# mapleCUx_large_088-Stripped.net
KiCad netlist of a schematic drawn in EAGLE
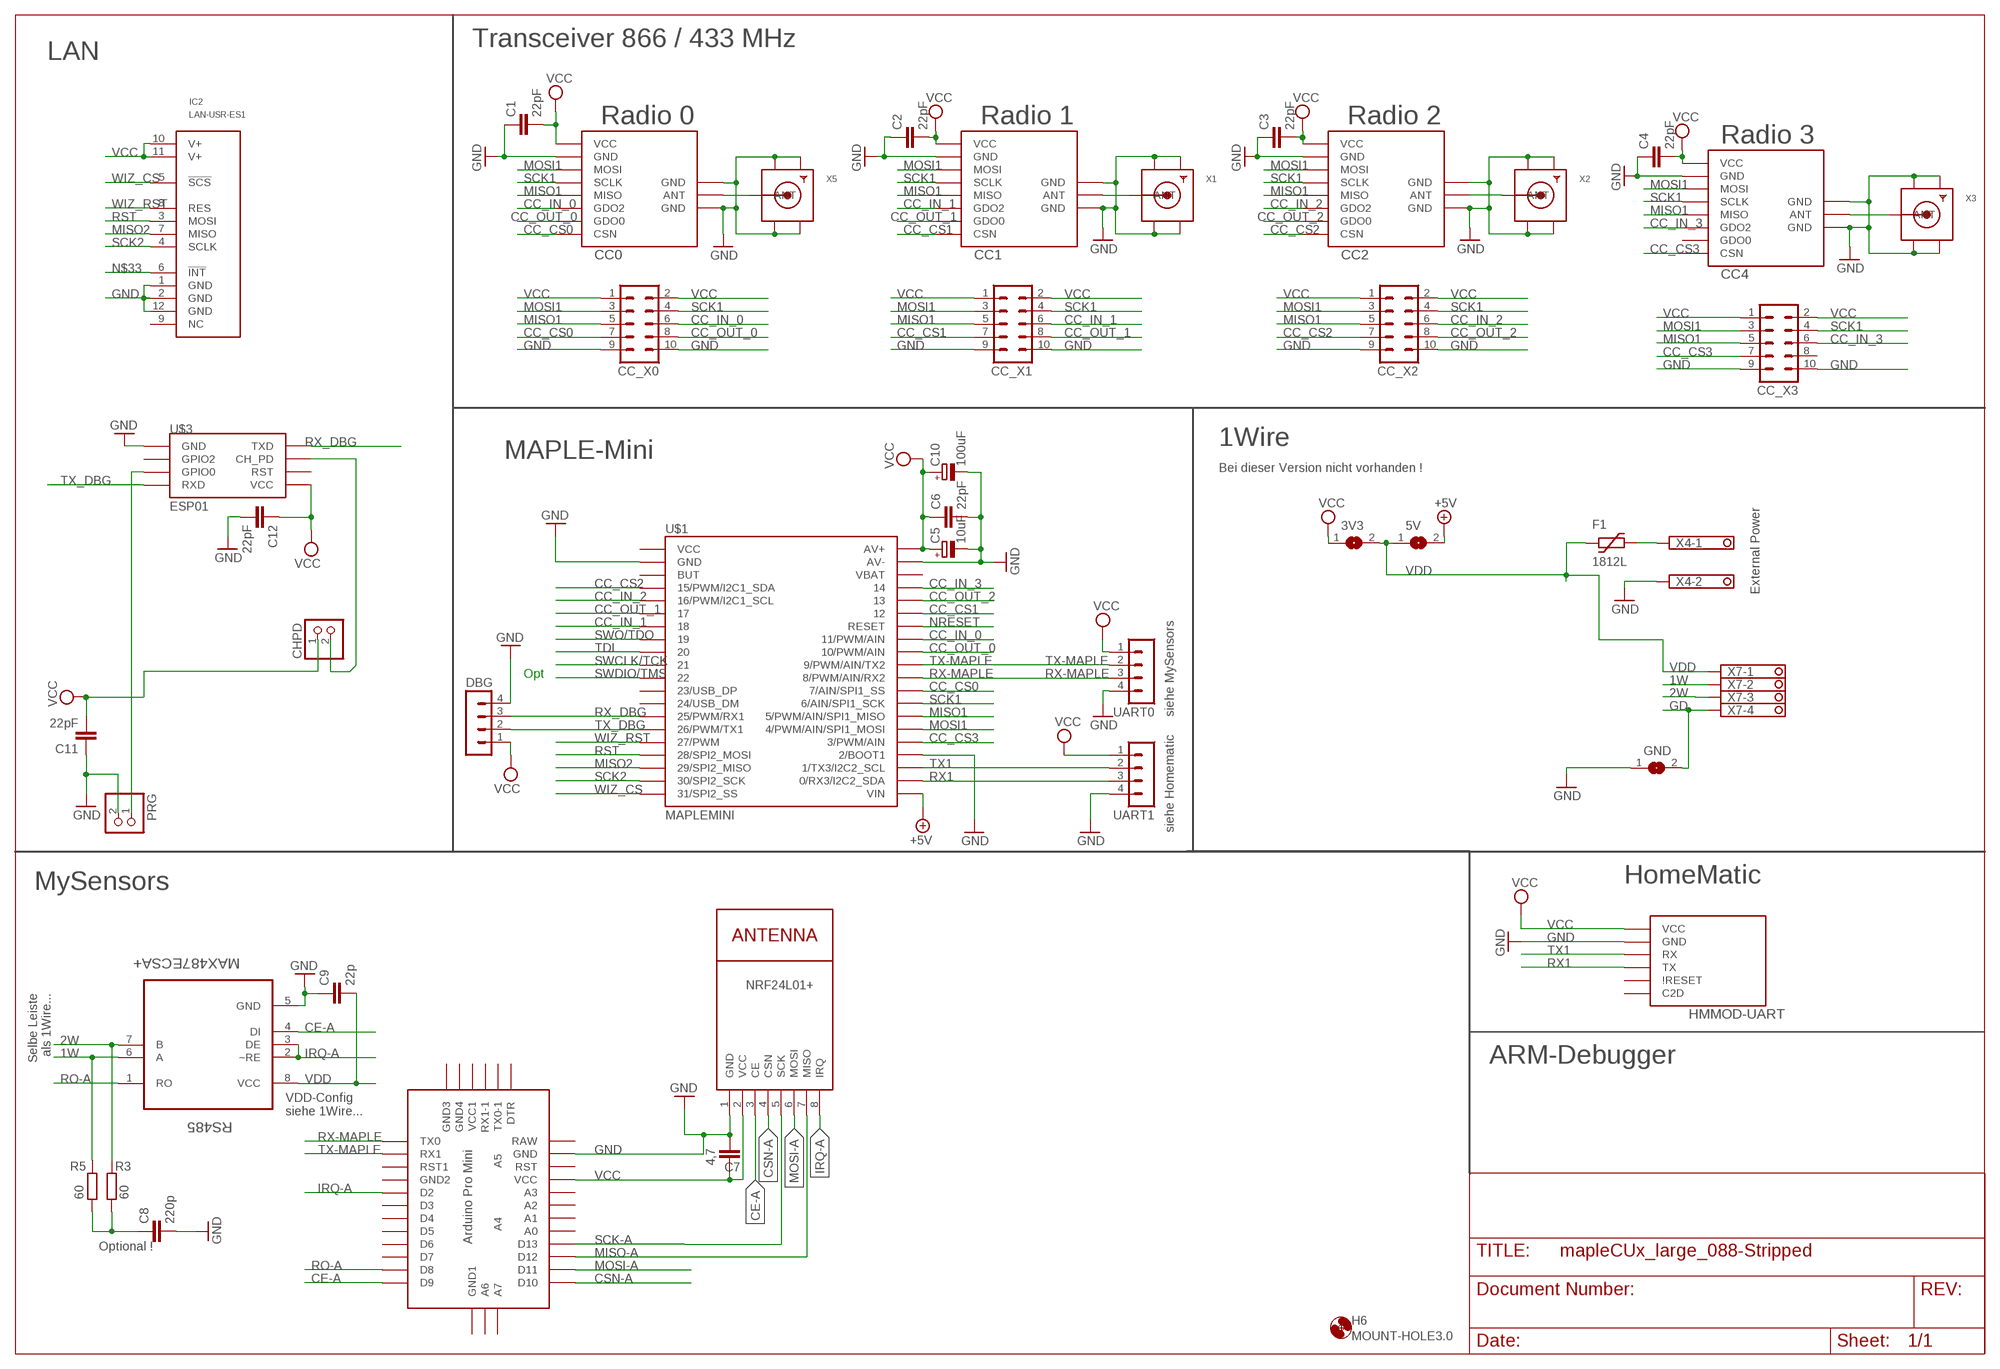
[diagram p0: schematic, sheet 1]

(export (version "E")
  (design (tool "Eeschema 10.0.6"))
  (components
    (comp (ref "3V3") (value "SJ") (footprint "eagle-import:SJ") (libsource (lib "eagle-import") (part "SJ")))
    (comp (ref "5V") (value "SJ") (footprint "eagle-import:SJ") (libsource (lib "eagle-import") (part "SJ")))
    (comp (ref "C1")
      (value "22pF")
      (footprint "eagle-import:C0805")
      (libsource (lib "eagle-import") (part "C-EUC0805"))
    )
    (comp (ref "C2")
      (value "22pF")
      (footprint "eagle-import:C0805")
      (libsource (lib "eagle-import") (part "C-EUC0805"))
    )
    (comp (ref "C3")
      (value "22pF")
      (footprint "eagle-import:C0805")
      (libsource (lib "eagle-import") (part "C-EUC0805"))
    )
    (comp (ref "C4")
      (value "22pF")
      (footprint "eagle-import:C0805")
      (libsource (lib "eagle-import") (part "C-EUC0805"))
    )
    (comp (ref "C5")
      (value "10uF")
      (footprint "eagle-import:R_2012-12W")
      (libsource (lib "eagle-import") (part "CPOL-EUR/2012-12W"))
    )
    (comp (ref "C6")
      (value "22pF")
      (footprint "eagle-import:C0805")
      (libsource (lib "eagle-import") (part "C-EUC0805"))
    )
    (comp (ref "C7")
      (value "4,7")
      (footprint "eagle-import:C1210")
      (libsource (lib "eagle-import") (part "C-EUC1210"))
    )
    (comp (ref "C8")
      (value "220p")
      (footprint "eagle-import:C0805")
      (libsource (lib "eagle-import") (part "C-EUC0805"))
    )
    (comp (ref "C9")
      (value "22p")
      (footprint "eagle-import:C0805")
      (libsource (lib "eagle-import") (part "C-EUC0805"))
    )
    (comp (ref "C10")
      (value "100uF")
      (footprint "eagle-import:E5-8,5")
      (libsource (lib "eagle-import") (part "CPOL-EUE5-8.5"))
    )
    (comp (ref "C11")
      (value "22pF")
      (footprint "eagle-import:C0805")
      (libsource (lib "eagle-import") (part "C-EUC0805"))
    )
    (comp (ref "C12")
      (value "22pF")
      (footprint "eagle-import:C0805")
      (libsource (lib "eagle-import") (part "C-EUC0805"))
    )
    (comp (ref "CC0")
      (value "CC1101")
      (footprint "eagle-import:CC1101_MODULE1_SMD")
      (libsource (lib "eagle-import") (part "CC1101_MODULE1SMD"))
    )
    (comp (ref "CC1")
      (value "CC1101_MODULE1SMD")
      (footprint "eagle-import:CC1101_MODULE1_SMD")
      (libsource (lib "eagle-import") (part "CC1101_MODULE1SMD"))
    )
    (comp (ref "CC2")
      (value "CC1101_MODULE1SMD")
      (footprint "eagle-import:CC1101_MODULE1_SMD")
      (libsource (lib "eagle-import") (part "CC1101_MODULE1SMD"))
    )
    (comp (ref "CC4")
      (value "CC1101_MODULE1SMD")
      (footprint "eagle-import:CC1101_MODULE1_SMD")
      (libsource (lib "eagle-import") (part "CC1101_MODULE1SMD"))
    )
    (comp (ref "CC_X0")
      (value "MA05-2")
      (footprint "eagle-import:MA05-2")
      (libsource (lib "eagle-import") (part "MA05-2"))
    )
    (comp (ref "CC_X1")
      (value "MA05-2")
      (footprint "eagle-import:MA05-2")
      (libsource (lib "eagle-import") (part "MA05-2"))
    )
    (comp (ref "CC_X2")
      (value "MA05-2")
      (footprint "eagle-import:MA05-2")
      (libsource (lib "eagle-import") (part "MA05-2"))
    )
    (comp (ref "CC_X3")
      (value "MA05-2")
      (footprint "eagle-import:MA05-2")
      (libsource (lib "eagle-import") (part "MA05-2"))
    )
    (comp (ref "CHPD")
      (value "PINHD-1X2")
      (footprint "eagle-import:1X02")
      (libsource (lib "eagle-import") (part "PINHD-1X2"))
    )
    (comp (ref "DBG")
      (value "MA04-1")
      (footprint "eagle-import:MA04-1")
      (libsource (lib "eagle-import") (part "MA04-1"))
    )
    (comp (ref "F1")
      (value "1812L")
      (footprint "eagle-import:1812L")
      (libsource (lib "eagle-import") (part "1812L"))
    )
    (comp (ref "GND") (value "SJ") (footprint "eagle-import:SJ") (libsource (lib "eagle-import") (part "SJ")))
    (comp (ref "H6")
      (value "MOUNT-HOLE3.0")
      (footprint "eagle-import:3,0")
      (libsource (lib "eagle-import") (part "MOUNT-HOLE3.0"))
    )
    (comp (ref "HMMOD-UART")
      (value "HM-MOD-UARTDIL")
      (footprint "eagle-import:HM-MOD-UART-DIL")
      (libsource (lib "eagle-import") (part "HM-MOD-UARTDIL"))
    )
    (comp (ref "IC2")
      (value "LAN-USR-ES1")
      (footprint "eagle-import:USR-ES1")
      (libsource (lib "eagle-import") (part "LAN-USR-ES1"))
    )
    (comp (ref "NRF24L01+")
      (value "NRF24L01+")
      (footprint "eagle-import:WIRELESS-NRF24L01")
      (libsource (lib "eagle-import") (part "WIRELESS-NRF24L01"))
    )
    (comp (ref "PRG")
      (value "PINHD-1X2")
      (footprint "eagle-import:1X02")
      (libsource (lib "eagle-import") (part "PINHD-1X2"))
    )
    (comp (ref "R3")
      (value "60")
      (footprint "eagle-import:R0805")
      (libsource (lib "eagle-import") (part "R-EU_R0805"))
    )
    (comp (ref "R5")
      (value "60")
      (footprint "eagle-import:R0805")
      (libsource (lib "eagle-import") (part "R-EU_R0805"))
    )
    (comp (ref "RS485")
      (value "MAX487ECSA+")
      (footprint "eagle-import:SOIC127P600X175-8N")
      (libsource (lib "eagle-import") (part "MAX487ECSA+"))
    )
    (comp (ref "U$1")
      (value "MAPLEMINI")
      (footprint "eagle-import:20-DIP")
      (libsource (lib "eagle-import") (part "MAPLEMINI"))
    )
    (comp (ref "U$2")
      (value "ABK-PRO-MINI")
      (footprint "eagle-import:ABK-PRO-MINI")
      (libsource (lib "eagle-import") (part "ABK-PRO-MINI"))
    )
    (comp (ref "U$3")
      (value "ESP01")
      (footprint "eagle-import:ESP01")
      (libsource (lib "eagle-import") (part "ESP01"))
    )
    (comp (ref "UART0")
      (value "MA04-1")
      (footprint "eagle-import:MA04-1")
      (libsource (lib "eagle-import") (part "MA04-1"))
    )
    (comp (ref "UART1")
      (value "MA04-1")
      (footprint "eagle-import:MA04-1")
      (libsource (lib "eagle-import") (part "MA04-1"))
    )
    (comp (ref "X1")
      (value "SMACONNECTOR_EDGE_UFL")
      (footprint "eagle-import:SMA_EDGELAUNCH_UFL")
      (libsource (lib "eagle-import") (part "SMACONNECTOR_EDGE_UFL"))
    )
    (comp (ref "X2")
      (value "SMACONNECTOR_EDGE_UFL")
      (footprint "eagle-import:SMA_EDGELAUNCH_UFL")
      (libsource (lib "eagle-import") (part "SMACONNECTOR_EDGE_UFL"))
    )
    (comp (ref "X3")
      (value "SMACONNECTOR_EDGE_UFL")
      (footprint "eagle-import:SMA_EDGELAUNCH_UFL")
      (libsource (lib "eagle-import") (part "SMACONNECTOR_EDGE_UFL"))
    )
    (comp (ref "X4")
      (value "1751248")
      (footprint "eagle-import:1751248")
      (libsource (lib "eagle-import") (part "1751248"))
    )
    (comp (ref "X5")
      (value "SMACONNECTOR_EDGE_UFL")
      (footprint "eagle-import:SMA_EDGELAUNCH_UFL")
      (libsource (lib "eagle-import") (part "SMACONNECTOR_EDGE_UFL"))
    )
    (comp (ref "X7")
      (value "1751264")
      (footprint "eagle-import:1751264")
      (libsource (lib "eagle-import") (part "1751264"))
    )
  )
  (nets
    (net (code "1") (name "+5V") (class "Default")
      (node (ref "5V") (pin "2") (pinfunction "2_2") (pintype "passive"))
      (node (ref "U$1") (pin "21") (pinfunction "VIN_21") (pintype "bidirectional"))
    )
    (net (code "2") (name "/1W") (class "Default")
      (node (ref "R5") (pin "2") (pinfunction "2_2") (pintype "passive"))
      (node (ref "RS485") (pin "6") (pinfunction "A_6") (pintype "bidirectional"))
      (node (ref "X7") (pin "2") (pinfunction "K_2") (pintype "passive"))
    )
    (net (code "3") (name "/2W") (class "Default")
      (node (ref "R3") (pin "2") (pinfunction "2_2") (pintype "passive"))
      (node (ref "RS485") (pin "7") (pinfunction "B_7") (pintype "bidirectional"))
      (node (ref "X7") (pin "3") (pinfunction "K_3") (pintype "passive"))
    )
    (net (code "4") (name "/CC_CS0") (class "Default")
      (node (ref "CC0") (pin "CSN") (pinfunction "CSN_CSN") (pintype "bidirectional"))
      (node (ref "CC_X0") (pin "7") (pinfunction "7_7") (pintype "passive"))
      (node (ref "U$1") (pin "29") (pinfunction "7/AIN/SPI1_SS_29") (pintype "bidirectional"))
    )
    (net (code "5") (name "/CC_CS1") (class "Default")
      (node (ref "CC1") (pin "CSN") (pinfunction "CSN_CSN") (pintype "bidirectional"))
      (node (ref "CC_X1") (pin "7") (pinfunction "7_7") (pintype "passive"))
      (node (ref "U$1") (pin "35") (pinfunction "12_35") (pintype "bidirectional"))
    )
    (net (code "6") (name "/CC_CS2") (class "Default")
      (node (ref "CC2") (pin "CSN") (pinfunction "CSN_CSN") (pintype "bidirectional"))
      (node (ref "CC_X2") (pin "7") (pinfunction "7_7") (pintype "passive"))
      (node (ref "U$1") (pin "4") (pinfunction "15/PWM/I2C1_SDA_4") (pintype "bidirectional"))
    )
    (net (code "7") (name "/CC_CS3") (class "Default")
      (node (ref "CC4") (pin "CSN") (pinfunction "CSN_CSN") (pintype "bidirectional"))
      (node (ref "CC_X3") (pin "7") (pinfunction "7_7") (pintype "passive"))
      (node (ref "U$1") (pin "25") (pinfunction "3/PWM/AIN_25") (pintype "bidirectional"))
    )
    (net (code "8") (name "/CC_IN_0") (class "Default")
      (node (ref "CC0") (pin "GDO2") (pinfunction "GDO2_GDO2") (pintype "bidirectional"))
      (node (ref "CC_X0") (pin "6") (pinfunction "6_6") (pintype "passive"))
      (node (ref "U$1") (pin "33") (pinfunction "11/PWM/AIN_33") (pintype "bidirectional"))
    )
    (net (code "9") (name "/CC_IN_1") (class "Default")
      (node (ref "CC1") (pin "GDO2") (pinfunction "GDO2_GDO2") (pintype "bidirectional"))
      (node (ref "CC_X1") (pin "6") (pinfunction "6_6") (pintype "passive"))
      (node (ref "U$1") (pin "7") (pinfunction "18_7") (pintype "bidirectional"))
    )
    (net (code "10") (name "/CC_IN_2") (class "Default")
      (node (ref "CC2") (pin "GDO2") (pinfunction "GDO2_GDO2") (pintype "bidirectional"))
      (node (ref "CC_X2") (pin "6") (pinfunction "6_6") (pintype "passive"))
      (node (ref "U$1") (pin "5") (pinfunction "16/PWM/I2C1_SCL_5") (pintype "bidirectional"))
    )
    (net (code "11") (name "/CC_IN_3") (class "Default")
      (node (ref "CC4") (pin "GDO2") (pinfunction "GDO2_GDO2") (pintype "bidirectional"))
      (node (ref "CC_X3") (pin "6") (pinfunction "6_6") (pintype "passive"))
      (node (ref "U$1") (pin "37") (pinfunction "14_37") (pintype "bidirectional"))
    )
    (net (code "12") (name "/CC_OUT_0") (class "Default")
      (node (ref "CC0") (pin "GDO0") (pinfunction "GDO0_GDO0") (pintype "bidirectional"))
      (node (ref "CC_X0") (pin "8") (pinfunction "8_8") (pintype "passive"))
      (node (ref "U$1") (pin "32") (pinfunction "10/PWM/AIN_32") (pintype "bidirectional"))
    )
    (net (code "13") (name "/CC_OUT_1") (class "Default")
      (node (ref "CC1") (pin "GDO0") (pinfunction "GDO0_GDO0") (pintype "bidirectional"))
      (node (ref "CC_X1") (pin "8") (pinfunction "8_8") (pintype "passive"))
      (node (ref "U$1") (pin "6") (pinfunction "17_6") (pintype "bidirectional"))
    )
    (net (code "14") (name "/CC_OUT_2") (class "Default")
      (node (ref "CC2") (pin "GDO0") (pinfunction "GDO0_GDO0") (pintype "bidirectional"))
      (node (ref "CC_X2") (pin "8") (pinfunction "8_8") (pintype "passive"))
      (node (ref "U$1") (pin "36") (pinfunction "13_36") (pintype "bidirectional"))
    )
    (net (code "15") (name "/GD") (class "Default")
      (node (ref "GND") (pin "2") (pinfunction "2_2") (pintype "passive"))
      (node (ref "X7") (pin "4") (pinfunction "K_4") (pintype "passive"))
    )
    (net (code "16") (name "/MISO-A") (class "Default")
      (node (ref "NRF24L01+") (pin "7") (pinfunction "MISO_7") (pintype "bidirectional"))
      (node (ref "U$2") (pin "D12") (pinfunction "D12_D12") (pintype "bidirectional"))
    )
    (net (code "17") (name "/MISO1") (class "Default")
      (node (ref "CC0") (pin "MISO") (pinfunction "MISO_MISO") (pintype "bidirectional"))
      (node (ref "CC1") (pin "MISO") (pinfunction "MISO_MISO") (pintype "bidirectional"))
      (node (ref "CC2") (pin "MISO") (pinfunction "MISO_MISO") (pintype "bidirectional"))
      (node (ref "CC4") (pin "MISO") (pinfunction "MISO_MISO") (pintype "bidirectional"))
      (node (ref "CC_X0") (pin "5") (pinfunction "5_5") (pintype "passive"))
      (node (ref "CC_X1") (pin "5") (pinfunction "5_5") (pintype "passive"))
      (node (ref "CC_X2") (pin "5") (pinfunction "5_5") (pintype "passive"))
      (node (ref "CC_X3") (pin "5") (pinfunction "5_5") (pintype "passive"))
      (node (ref "U$1") (pin "27") (pinfunction "5/PWM/AIN/SPI1_MISO_27") (pintype "bidirectional"))
    )
    (net (code "18") (name "/MISO2") (class "Default")
      (node (ref "IC2") (pin "7") (pinfunction "MISO_7") (pintype "bidirectional"))
      (node (ref "U$1") (pin "18") (pinfunction "29/SPI2_MISO_18") (pintype "bidirectional"))
    )
    (net (code "19") (name "/MOSI1") (class "Default")
      (node (ref "CC0") (pin "MOSI") (pinfunction "MOSI_MOSI") (pintype "bidirectional"))
      (node (ref "CC1") (pin "MOSI") (pinfunction "MOSI_MOSI") (pintype "bidirectional"))
      (node (ref "CC2") (pin "MOSI") (pinfunction "MOSI_MOSI") (pintype "bidirectional"))
      (node (ref "CC4") (pin "MOSI") (pinfunction "MOSI_MOSI") (pintype "bidirectional"))
      (node (ref "CC_X0") (pin "3") (pinfunction "3_3") (pintype "passive"))
      (node (ref "CC_X1") (pin "3") (pinfunction "3_3") (pintype "passive"))
      (node (ref "CC_X2") (pin "3") (pinfunction "3_3") (pintype "passive"))
      (node (ref "CC_X3") (pin "3") (pinfunction "3_3") (pintype "passive"))
      (node (ref "U$1") (pin "26") (pinfunction "4/PWM/AIN/SPI1_MOSI_26") (pintype "bidirectional"))
    )
    (net (code "20") (name "/N$33") (class "Default")
      (node (ref "IC2") (pin "6") (pinfunction "~{INT}_6") (pintype "output"))
    )
    (net (code "21") (name "/NRESET") (class "Default")
      (node (ref "U$1") (pin "34") (pinfunction "RESET_34") (pintype "bidirectional"))
    )
    (net (code "22") (name "/RO-A") (class "Default")
      (node (ref "RS485") (pin "1") (pinfunction "RO_1") (pintype "output"))
      (node (ref "U$2") (pin "D8") (pinfunction "D8_D8") (pintype "bidirectional"))
    )
    (net (code "23") (name "/RST") (class "Default")
      (node (ref "IC2") (pin "3") (pinfunction "MOSI_3") (pintype "bidirectional"))
      (node (ref "U$1") (pin "17") (pinfunction "28/SPI2_MOSI_17") (pintype "bidirectional"))
    )
    (net (code "24") (name "/RX-MAPLE") (class "Default")
      (node (ref "U$1") (pin "30") (pinfunction "8/PWM/AIN/RX2_30") (pintype "bidirectional"))
      (node (ref "U$2") (pin "TX0") (pinfunction "TX0_TX0") (pintype "bidirectional"))
      (node (ref "UART0") (pin "3") (pinfunction "3_3") (pintype "passive"))
    )
    (net (code "25") (name "/RX1") (class "Default")
      (node (ref "HMMOD-UART") (pin "5") (pinfunction "TX_5") (pintype "bidirectional"))
      (node (ref "U$1") (pin "22") (pinfunction "0/RX3/I2C2_SDA_22") (pintype "bidirectional"))
      (node (ref "UART1") (pin "3") (pinfunction "3_3") (pintype "passive"))
    )
    (net (code "26") (name "/RX_DBG") (class "Default")
      (node (ref "DBG") (pin "3") (pinfunction "3_3") (pintype "passive"))
      (node (ref "U$1") (pin "14") (pinfunction "25/PWM/RX1_14") (pintype "bidirectional"))
      (node (ref "U$3") (pin "TX") (pinfunction "TXD_TX") (pintype "bidirectional"))
    )
    (net (code "27") (name "/SCK-A") (class "Default")
      (node (ref "NRF24L01+") (pin "5") (pinfunction "SCK_5") (pintype "bidirectional"))
      (node (ref "U$2") (pin "D13") (pinfunction "D13_D13") (pintype "bidirectional"))
    )
    (net (code "28") (name "/SCK1") (class "Default")
      (node (ref "CC0") (pin "SCLK") (pinfunction "SCLK_SCLK") (pintype "bidirectional"))
      (node (ref "CC1") (pin "SCLK") (pinfunction "SCLK_SCLK") (pintype "bidirectional"))
      (node (ref "CC2") (pin "SCLK") (pinfunction "SCLK_SCLK") (pintype "bidirectional"))
      (node (ref "CC4") (pin "SCLK") (pinfunction "SCLK_SCLK") (pintype "bidirectional"))
      (node (ref "CC_X0") (pin "4") (pinfunction "4_4") (pintype "passive"))
      (node (ref "CC_X1") (pin "4") (pinfunction "4_4") (pintype "passive"))
      (node (ref "CC_X2") (pin "4") (pinfunction "4_4") (pintype "passive"))
      (node (ref "CC_X3") (pin "4") (pinfunction "4_4") (pintype "passive"))
      (node (ref "U$1") (pin "28") (pinfunction "6/AIN/SPI1_SCK_28") (pintype "bidirectional"))
    )
    (net (code "29") (name "/SCK2") (class "Default")
      (node (ref "IC2") (pin "4") (pinfunction "SCLK_4") (pintype "input"))
      (node (ref "U$1") (pin "19") (pinfunction "30/SPI2_SCK_19") (pintype "bidirectional"))
    )
    (net (code "30") (name "/SWCLK{slash}TCK") (class "Default")
      (node (ref "U$1") (pin "10") (pinfunction "21_10") (pintype "bidirectional"))
    )
    (net (code "31") (name "/SWDIO{slash}TMS") (class "Default")
      (node (ref "U$1") (pin "11") (pinfunction "22_11") (pintype "bidirectional"))
    )
    (net (code "32") (name "/SWO{slash}TDO") (class "Default")
      (node (ref "U$1") (pin "8") (pinfunction "19_8") (pintype "bidirectional"))
    )
    (net (code "33") (name "/TDI") (class "Default")
      (node (ref "U$1") (pin "9") (pinfunction "20_9") (pintype "bidirectional"))
    )
    (net (code "34") (name "/TX-MAPLE") (class "Default")
      (node (ref "U$1") (pin "31") (pinfunction "9/PWM/AIN/TX2_31") (pintype "bidirectional"))
      (node (ref "U$2") (pin "RX1") (pinfunction "RX1_RX1") (pintype "bidirectional"))
      (node (ref "UART0") (pin "2") (pinfunction "2_2") (pintype "passive"))
    )
    (net (code "35") (name "/TX1") (class "Default")
      (node (ref "HMMOD-UART") (pin "6") (pinfunction "RX_6") (pintype "bidirectional"))
      (node (ref "U$1") (pin "23") (pinfunction "1/TX3/I2C2_SCL_23") (pintype "bidirectional"))
      (node (ref "UART1") (pin "2") (pinfunction "2_2") (pintype "passive"))
    )
    (net (code "36") (name "/TX_DBG") (class "Default")
      (node (ref "DBG") (pin "2") (pinfunction "2_2") (pintype "passive"))
      (node (ref "U$1") (pin "15") (pinfunction "26/PWM/TX1_15") (pintype "bidirectional"))
      (node (ref "U$3") (pin "RX") (pinfunction "RXD_RX") (pintype "bidirectional"))
    )
    (net (code "37") (name "/VDD") (class "Default")
      (node (ref "3V3") (pin "2") (pinfunction "2_2") (pintype "passive"))
      (node (ref "5V") (pin "1") (pinfunction "1_1") (pintype "passive"))
      (node (ref "C9") (pin "2") (pinfunction "2_2") (pintype "passive"))
      (node (ref "F1") (pin "P$1") (pinfunction "1_P$1") (pintype "passive"))
      (node (ref "RS485") (pin "8") (pinfunction "VCC_8") (pintype "power_in"))
      (node (ref "X7") (pin "1") (pinfunction "K_1") (pintype "passive"))
    )
    (net (code "38") (name "/WIZ_CS") (class "Default")
      (node (ref "IC2") (pin "5") (pinfunction "~{SCS}_5") (pintype "input"))
      (node (ref "U$1") (pin "20") (pinfunction "31/SPI2_SS_20") (pintype "bidirectional"))
    )
    (net (code "39") (name "/WIZ_RST") (class "Default")
      (node (ref "IC2") (pin "8") (pinfunction "RES_8") (pintype "input"))
      (node (ref "U$1") (pin "16") (pinfunction "27/PWM_16") (pintype "bidirectional"))
    )
    (net (code "40") (name "CE-A") (class "Default")
      (node (ref "NRF24L01+") (pin "3") (pinfunction "CE_3") (pintype "bidirectional"))
      (node (ref "RS485") (pin "4") (pinfunction "DI_4") (pintype "input"))
      (node (ref "U$2") (pin "D9") (pinfunction "D9_D9") (pintype "bidirectional"))
    )
    (net (code "41") (name "CSN-A") (class "Default")
      (node (ref "NRF24L01+") (pin "4") (pinfunction "CSN_4") (pintype "bidirectional"))
      (node (ref "U$2") (pin "D10") (pinfunction "D10_D10") (pintype "bidirectional"))
    )
    (net (code "42") (name "GND") (class "Default")
      (node (ref "C1") (pin "1") (pinfunction "1_1") (pintype "passive"))
      (node (ref "C10") (pin "-") (pinfunction "-_-") (pintype "passive"))
      (node (ref "C11") (pin "1") (pinfunction "1_1") (pintype "passive"))
      (node (ref "C12") (pin "2") (pinfunction "2_2") (pintype "passive"))
      (node (ref "C2") (pin "1") (pinfunction "1_1") (pintype "passive"))
      (node (ref "C3") (pin "1") (pinfunction "1_1") (pintype "passive"))
      (node (ref "C4") (pin "1") (pinfunction "1_1") (pintype "passive"))
      (node (ref "C5") (pin "-") (pinfunction "-_-") (pintype "passive"))
      (node (ref "C6") (pin "2") (pinfunction "2_2") (pintype "passive"))
      (node (ref "C7") (pin "1") (pinfunction "1_1") (pintype "passive"))
      (node (ref "C8") (pin "2") (pinfunction "2_2") (pintype "passive"))
      (node (ref "C9") (pin "1") (pinfunction "1_1") (pintype "passive"))
      (node (ref "CC0") (pin "GND@0") (pinfunction "GND_GND@0") (pintype "power_in"))
      (node (ref "CC0") (pin "GND@1") (pinfunction "GND_GND@1") (pintype "power_in"))
      (node (ref "CC0") (pin "GND@2") (pinfunction "GND_GND@2") (pintype "power_in"))
      (node (ref "CC1") (pin "GND@0") (pinfunction "GND_GND@0") (pintype "power_in"))
      (node (ref "CC1") (pin "GND@1") (pinfunction "GND_GND@1") (pintype "power_in"))
      (node (ref "CC1") (pin "GND@2") (pinfunction "GND_GND@2") (pintype "power_in"))
      (node (ref "CC2") (pin "GND@0") (pinfunction "GND_GND@0") (pintype "power_in"))
      (node (ref "CC2") (pin "GND@1") (pinfunction "GND_GND@1") (pintype "power_in"))
      (node (ref "CC2") (pin "GND@2") (pinfunction "GND_GND@2") (pintype "power_in"))
      (node (ref "CC4") (pin "GND@0") (pinfunction "GND_GND@0") (pintype "power_in"))
      (node (ref "CC4") (pin "GND@1") (pinfunction "GND_GND@1") (pintype "power_in"))
      (node (ref "CC4") (pin "GND@2") (pinfunction "GND_GND@2") (pintype "power_in"))
      (node (ref "CC_X0") (pin "10") (pinfunction "10_10") (pintype "passive"))
      (node (ref "CC_X0") (pin "9") (pinfunction "9_9") (pintype "passive"))
      (node (ref "CC_X1") (pin "10") (pinfunction "10_10") (pintype "passive"))
      (node (ref "CC_X1") (pin "9") (pinfunction "9_9") (pintype "passive"))
      (node (ref "CC_X2") (pin "10") (pinfunction "10_10") (pintype "passive"))
      (node (ref "CC_X2") (pin "9") (pinfunction "9_9") (pintype "passive"))
      (node (ref "CC_X3") (pin "10") (pinfunction "10_10") (pintype "passive"))
      (node (ref "CC_X3") (pin "9") (pinfunction "9_9") (pintype "passive"))
      (node (ref "DBG") (pin "4") (pinfunction "4_4") (pintype "passive"))
      (node (ref "GND") (pin "1") (pinfunction "1_1") (pintype "passive"))
      (node (ref "HMMOD-UART") (pin "2") (pinfunction "GND_2") (pintype "power_in"))
      (node (ref "IC2") (pin "1") (pinfunction "GND_1") (pintype "power_in"))
      (node (ref "IC2") (pin "12") (pinfunction "GND_12") (pintype "power_in"))
      (node (ref "IC2") (pin "2") (pinfunction "GND_2") (pintype "power_in"))
      (node (ref "NRF24L01+") (pin "1") (pinfunction "GND_1") (pintype "power_in"))
      (node (ref "PRG") (pin "2") (pinfunction "2_2") (pintype "passive"))
      (node (ref "RS485") (pin "5") (pinfunction "GND_5") (pintype "passive"))
      (node (ref "U$1") (pin "2") (pinfunction "GND_2") (pintype "bidirectional"))
      (node (ref "U$1") (pin "24") (pinfunction "2/BOOT1_24") (pintype "bidirectional"))
      (node (ref "U$1") (pin "39") (pinfunction "AV-_39") (pintype "bidirectional"))
      (node (ref "U$2") (pin "GND") (pinfunction "GND_GND") (pintype "bidirectional"))
      (node (ref "U$3") (pin "GND") (pinfunction "GND_GND") (pintype "bidirectional"))
      (node (ref "UART0") (pin "4") (pinfunction "4_4") (pintype "passive"))
      (node (ref "UART1") (pin "4") (pinfunction "4_4") (pintype "passive"))
      (node (ref "X1") (pin "GND@1") (pinfunction "GND1_GND@1") (pintype "power_in"))
      (node (ref "X1") (pin "GND@2") (pinfunction "GND2_GND@2") (pintype "power_in"))
      (node (ref "X1") (pin "GND@3") (pinfunction "GND3_GND@3") (pintype "power_in"))
      (node (ref "X1") (pin "GND@4") (pinfunction "GND4_GND@4") (pintype "power_in"))
      (node (ref "X2") (pin "GND@1") (pinfunction "GND1_GND@1") (pintype "power_in"))
      (node (ref "X2") (pin "GND@2") (pinfunction "GND2_GND@2") (pintype "power_in"))
      (node (ref "X2") (pin "GND@3") (pinfunction "GND3_GND@3") (pintype "power_in"))
      (node (ref "X2") (pin "GND@4") (pinfunction "GND4_GND@4") (pintype "power_in"))
      (node (ref "X3") (pin "GND@1") (pinfunction "GND1_GND@1") (pintype "power_in"))
      (node (ref "X3") (pin "GND@2") (pinfunction "GND2_GND@2") (pintype "power_in"))
      (node (ref "X3") (pin "GND@3") (pinfunction "GND3_GND@3") (pintype "power_in"))
      (node (ref "X3") (pin "GND@4") (pinfunction "GND4_GND@4") (pintype "power_in"))
      (node (ref "X4") (pin "2") (pinfunction "K_2") (pintype "passive"))
      (node (ref "X5") (pin "GND@1") (pinfunction "GND1_GND@1") (pintype "power_in"))
      (node (ref "X5") (pin "GND@2") (pinfunction "GND2_GND@2") (pintype "power_in"))
      (node (ref "X5") (pin "GND@3") (pinfunction "GND3_GND@3") (pintype "power_in"))
      (node (ref "X5") (pin "GND@4") (pinfunction "GND4_GND@4") (pintype "power_in"))
    )
    (net (code "43") (name "IRQ-A") (class "Default")
      (node (ref "NRF24L01+") (pin "8") (pinfunction "IRQ_8") (pintype "bidirectional"))
      (node (ref "RS485") (pin "2") (pinfunction "~{RE}_2") (pintype "input"))
      (node (ref "RS485") (pin "3") (pinfunction "DE_3") (pintype "input"))
      (node (ref "U$2") (pin "D2") (pinfunction "D2_D2") (pintype "bidirectional"))
    )
    (net (code "44") (name "MOSI-A") (class "Default")
      (node (ref "NRF24L01+") (pin "6") (pinfunction "MOSI_6") (pintype "bidirectional"))
      (node (ref "U$2") (pin "D11") (pinfunction "D11_D11") (pintype "bidirectional"))
    )
    (net (code "45") (name "Net-(C8-Pad1)") (class "Default")
      (node (ref "C8") (pin "1") (pinfunction "1_1") (pintype "passive"))
      (node (ref "R3") (pin "1") (pinfunction "1_1") (pintype "passive"))
      (node (ref "R5") (pin "1") (pinfunction "1_1") (pintype "passive"))
    )
    (net (code "46") (name "Net-(CHPD-Pad2)") (class "Default")
      (node (ref "CHPD") (pin "2") (pinfunction "2_2") (pintype "passive"))
      (node (ref "U$3") (pin "CH_PD") (pinfunction "CH_PD_CH_PD") (pintype "bidirectional"))
    )
    (net (code "47") (name "Net-(F1-2)") (class "Default")
      (node (ref "F1") (pin "P$2") (pinfunction "2_P$2") (pintype "passive"))
      (node (ref "X4") (pin "1") (pinfunction "K_1") (pintype "passive"))
    )
    (net (code "48") (name "Net-(PRG-Pad1)") (class "Default")
      (node (ref "PRG") (pin "1") (pinfunction "1_1") (pintype "passive"))
      (node (ref "U$3") (pin "GPIO0") (pinfunction "GPIO0_GPIO0") (pintype "bidirectional"))
    )
    (net (code "49") (name "Net-(X1-ANT)") (class "Default")
      (node (ref "CC1") (pin "ANT") (pinfunction "ANT_ANT") (pintype "output"))
      (node (ref "X1") (pin "P") (pinfunction "ANT_P") (pintype "bidirectional"))
    )
    (net (code "50") (name "Net-(X2-ANT)") (class "Default")
      (node (ref "CC2") (pin "ANT") (pinfunction "ANT_ANT") (pintype "output"))
      (node (ref "X2") (pin "P") (pinfunction "ANT_P") (pintype "bidirectional"))
    )
    (net (code "51") (name "Net-(X3-ANT)") (class "Default")
      (node (ref "CC4") (pin "ANT") (pinfunction "ANT_ANT") (pintype "output"))
      (node (ref "X3") (pin "P") (pinfunction "ANT_P") (pintype "bidirectional"))
    )
    (net (code "52") (name "Net-(X5-ANT)") (class "Default")
      (node (ref "CC0") (pin "ANT") (pinfunction "ANT_ANT") (pintype "output"))
      (node (ref "X5") (pin "P") (pinfunction "ANT_P") (pintype "bidirectional"))
    )
    (net (code "53") (name "VCC") (class "Default")
      (node (ref "3V3") (pin "1") (pinfunction "1_1") (pintype "passive"))
      (node (ref "C1") (pin "2") (pinfunction "2_2") (pintype "passive"))
      (node (ref "C10") (pin "+") (pinfunction "+_+") (pintype "passive"))
      (node (ref "C11") (pin "2") (pinfunction "2_2") (pintype "passive"))
      (node (ref "C12") (pin "1") (pinfunction "1_1") (pintype "passive"))
      (node (ref "C2") (pin "2") (pinfunction "2_2") (pintype "passive"))
      (node (ref "C3") (pin "2") (pinfunction "2_2") (pintype "passive"))
      (node (ref "C4") (pin "2") (pinfunction "2_2") (pintype "passive"))
      (node (ref "C5") (pin "+") (pinfunction "+_+") (pintype "passive"))
      (node (ref "C6") (pin "1") (pinfunction "1_1") (pintype "passive"))
      (node (ref "C7") (pin "2") (pinfunction "2_2") (pintype "passive"))
      (node (ref "CC0") (pin "VCC") (pinfunction "VCC_VCC") (pintype "power_in"))
      (node (ref "CC1") (pin "VCC") (pinfunction "VCC_VCC") (pintype "power_in"))
      (node (ref "CC2") (pin "VCC") (pinfunction "VCC_VCC") (pintype "power_in"))
      (node (ref "CC4") (pin "VCC") (pinfunction "VCC_VCC") (pintype "power_in"))
      (node (ref "CC_X0") (pin "1") (pinfunction "1_1") (pintype "passive"))
      (node (ref "CC_X0") (pin "2") (pinfunction "2_2") (pintype "passive"))
      (node (ref "CC_X1") (pin "1") (pinfunction "1_1") (pintype "passive"))
      (node (ref "CC_X1") (pin "2") (pinfunction "2_2") (pintype "passive"))
      (node (ref "CC_X2") (pin "1") (pinfunction "1_1") (pintype "passive"))
      (node (ref "CC_X2") (pin "2") (pinfunction "2_2") (pintype "passive"))
      (node (ref "CC_X3") (pin "1") (pinfunction "1_1") (pintype "passive"))
      (node (ref "CC_X3") (pin "2") (pinfunction "2_2") (pintype "passive"))
      (node (ref "CHPD") (pin "1") (pinfunction "1_1") (pintype "passive"))
      (node (ref "DBG") (pin "1") (pinfunction "1_1") (pintype "passive"))
      (node (ref "HMMOD-UART") (pin "1") (pinfunction "VCC_1") (pintype "power_in"))
      (node (ref "IC2") (pin "10") (pinfunction "V+_10") (pintype "power_in"))
      (node (ref "IC2") (pin "11") (pinfunction "V+_11") (pintype "power_in"))
      (node (ref "NRF24L01+") (pin "2") (pinfunction "VCC_2") (pintype "power_in"))
      (node (ref "U$1") (pin "40") (pinfunction "AV+_40") (pintype "bidirectional"))
      (node (ref "U$2") (pin "VCC") (pinfunction "VCC_VCC") (pintype "bidirectional"))
      (node (ref "U$3") (pin "VCC") (pinfunction "VCC_VCC") (pintype "bidirectional"))
      (node (ref "UART0") (pin "1") (pinfunction "1_1") (pintype "passive"))
      (node (ref "UART1") (pin "1") (pinfunction "1_1") (pintype "passive"))
    )
    (net (code "54") (name "unconnected-(CC4-PadGDO0)") (class "Default")
      (node (ref "CC4") (pin "GDO0") (pinfunction "GDO0_GDO0") (pintype "bidirectional"))
    )
    (net (code "55") (name "unconnected-(CC_X3-Pad8)") (class "Default")
      (node (ref "CC_X3") (pin "8") (pinfunction "8_8") (pintype "passive"))
    )
    (net (code "56") (name "unconnected-(HMMOD-UART-C2D-Pad3)") (class "Default")
      (node (ref "HMMOD-UART") (pin "3") (pinfunction "C2D_3") (pintype "bidirectional"))
    )
    (net (code "57") (name "unconnected-(HMMOD-UART-\\~{RESET}-Pad4)") (class "Default")
      (node (ref "HMMOD-UART") (pin "4") (pinfunction "\\~{RESET}_4") (pintype "bidirectional"))
    )
    (net (code "58") (name "unconnected-(IC2-NC-Pad9)") (class "Default")
      (node (ref "IC2") (pin "9") (pinfunction "NC_9") (pintype "no_connect"))
    )
    (net (code "59") (name "unconnected-(U$1-23{slash}USB_DP-Pad12)") (class "Default")
      (node (ref "U$1") (pin "12") (pinfunction "23/USB_DP_12") (pintype "bidirectional"))
    )
    (net (code "60") (name "unconnected-(U$1-24{slash}USB_DM-Pad13)") (class "Default")
      (node (ref "U$1") (pin "13") (pinfunction "24/USB_DM_13") (pintype "bidirectional"))
    )
    (net (code "61") (name "unconnected-(U$1-BUT-Pad3)") (class "Default")
      (node (ref "U$1") (pin "3") (pinfunction "BUT_3") (pintype "bidirectional"))
    )
    (net (code "62") (name "unconnected-(U$1-VBAT-Pad38)") (class "Default")
      (node (ref "U$1") (pin "38") (pinfunction "VBAT_38") (pintype "bidirectional"))
    )
    (net (code "63") (name "unconnected-(U$1-VCC-Pad1)") (class "Default")
      (node (ref "U$1") (pin "1") (pinfunction "VCC_1") (pintype "bidirectional"))
    )
    (net (code "64") (name "unconnected-(U$2-GND1-PadGND4)") (class "Default")
      (node (ref "U$2") (pin "GND4") (pinfunction "GND1_GND4") (pintype "bidirectional"))
    )
    (net (code "65") (name "unconnected-(U$2-GND2-PadGND1)") (class "Default")
      (node (ref "U$2") (pin "GND1") (pinfunction "GND2_GND1") (pintype "bidirectional"))
    )
    (net (code "66") (name "unconnected-(U$2-GND3-PadGND2)") (class "Default")
      (node (ref "U$2") (pin "GND2") (pinfunction "GND3_GND2") (pintype "bidirectional"))
    )
    (net (code "67") (name "unconnected-(U$2-GND4-PadGND3)") (class "Default")
      (node (ref "U$2") (pin "GND3") (pinfunction "GND4_GND3") (pintype "bidirectional"))
    )
    (net (code "68") (name "unconnected-(U$2-PadA0)") (class "Default")
      (node (ref "U$2") (pin "A0") (pinfunction "A0_A0") (pintype "bidirectional"))
    )
    (net (code "69") (name "unconnected-(U$2-PadA1)") (class "Default")
      (node (ref "U$2") (pin "A1") (pinfunction "A1_A1") (pintype "bidirectional"))
    )
    (net (code "70") (name "unconnected-(U$2-PadA2)") (class "Default")
      (node (ref "U$2") (pin "A2") (pinfunction "A2_A2") (pintype "bidirectional"))
    )
    (net (code "71") (name "unconnected-(U$2-PadA3)") (class "Default")
      (node (ref "U$2") (pin "A3") (pinfunction "A3_A3") (pintype "bidirectional"))
    )
    (net (code "72") (name "unconnected-(U$2-PadA4)") (class "Default")
      (node (ref "U$2") (pin "A4") (pinfunction "A4_A4") (pintype "bidirectional"))
    )
    (net (code "73") (name "unconnected-(U$2-PadA5)") (class "Default")
      (node (ref "U$2") (pin "A5") (pinfunction "A5_A5") (pintype "bidirectional"))
    )
    (net (code "74") (name "unconnected-(U$2-PadA6)") (class "Default")
      (node (ref "U$2") (pin "A6") (pinfunction "A6_A6") (pintype "bidirectional"))
    )
    (net (code "75") (name "unconnected-(U$2-PadA7)") (class "Default")
      (node (ref "U$2") (pin "A7") (pinfunction "A7_A7") (pintype "bidirectional"))
    )
    (net (code "76") (name "unconnected-(U$2-PadD3)") (class "Default")
      (node (ref "U$2") (pin "D3") (pinfunction "D3_D3") (pintype "bidirectional"))
    )
    (net (code "77") (name "unconnected-(U$2-PadD4)") (class "Default")
      (node (ref "U$2") (pin "D4") (pinfunction "D4_D4") (pintype "bidirectional"))
    )
    (net (code "78") (name "unconnected-(U$2-PadD5)") (class "Default")
      (node (ref "U$2") (pin "D5") (pinfunction "D5_D5") (pintype "bidirectional"))
    )
    (net (code "79") (name "unconnected-(U$2-PadD6)") (class "Default")
      (node (ref "U$2") (pin "D6") (pinfunction "D6_D6") (pintype "bidirectional"))
    )
    (net (code "80") (name "unconnected-(U$2-PadD7)") (class "Default")
      (node (ref "U$2") (pin "D7") (pinfunction "D7_D7") (pintype "bidirectional"))
    )
    (net (code "81") (name "unconnected-(U$2-PadDTR)") (class "Default")
      (node (ref "U$2") (pin "DTR") (pinfunction "DTR_DTR") (pintype "bidirectional"))
    )
    (net (code "82") (name "unconnected-(U$2-PadRAW)") (class "Default")
      (node (ref "U$2") (pin "RAW") (pinfunction "RAW_RAW") (pintype "bidirectional"))
    )
    (net (code "83") (name "unconnected-(U$2-PadRST)") (class "Default")
      (node (ref "U$2") (pin "RST") (pinfunction "RST_RST") (pintype "bidirectional"))
    )
    (net (code "84") (name "unconnected-(U$2-PadRST1)") (class "Default")
      (node (ref "U$2") (pin "RST1") (pinfunction "RST1_RST1") (pintype "bidirectional"))
    )
    (net (code "85") (name "unconnected-(U$2-PadRX1-1)") (class "Default")
      (node (ref "U$2") (pin "RX1-1") (pinfunction "RX1-1_RX1-1") (pintype "bidirectional"))
    )
    (net (code "86") (name "unconnected-(U$2-PadTX0-1)") (class "Default")
      (node (ref "U$2") (pin "TX0-1") (pinfunction "TX0-1_TX0-1") (pintype "bidirectional"))
    )
    (net (code "87") (name "unconnected-(U$2-PadVCC1)") (class "Default")
      (node (ref "U$2") (pin "VCC1") (pinfunction "VCC1_VCC1") (pintype "bidirectional"))
    )
    (net (code "88") (name "unconnected-(U$3-PadGPIO2)") (class "Default")
      (node (ref "U$3") (pin "GPIO2") (pinfunction "GPIO2_GPIO2") (pintype "bidirectional"))
    )
    (net (code "89") (name "unconnected-(U$3-PadRST)") (class "Default")
      (node (ref "U$3") (pin "RST") (pinfunction "RST_RST") (pintype "bidirectional"))
    )
  )
)
